# Ethernet_PHY.net
KiCad netlist of a schematic drawn in Altium Designer
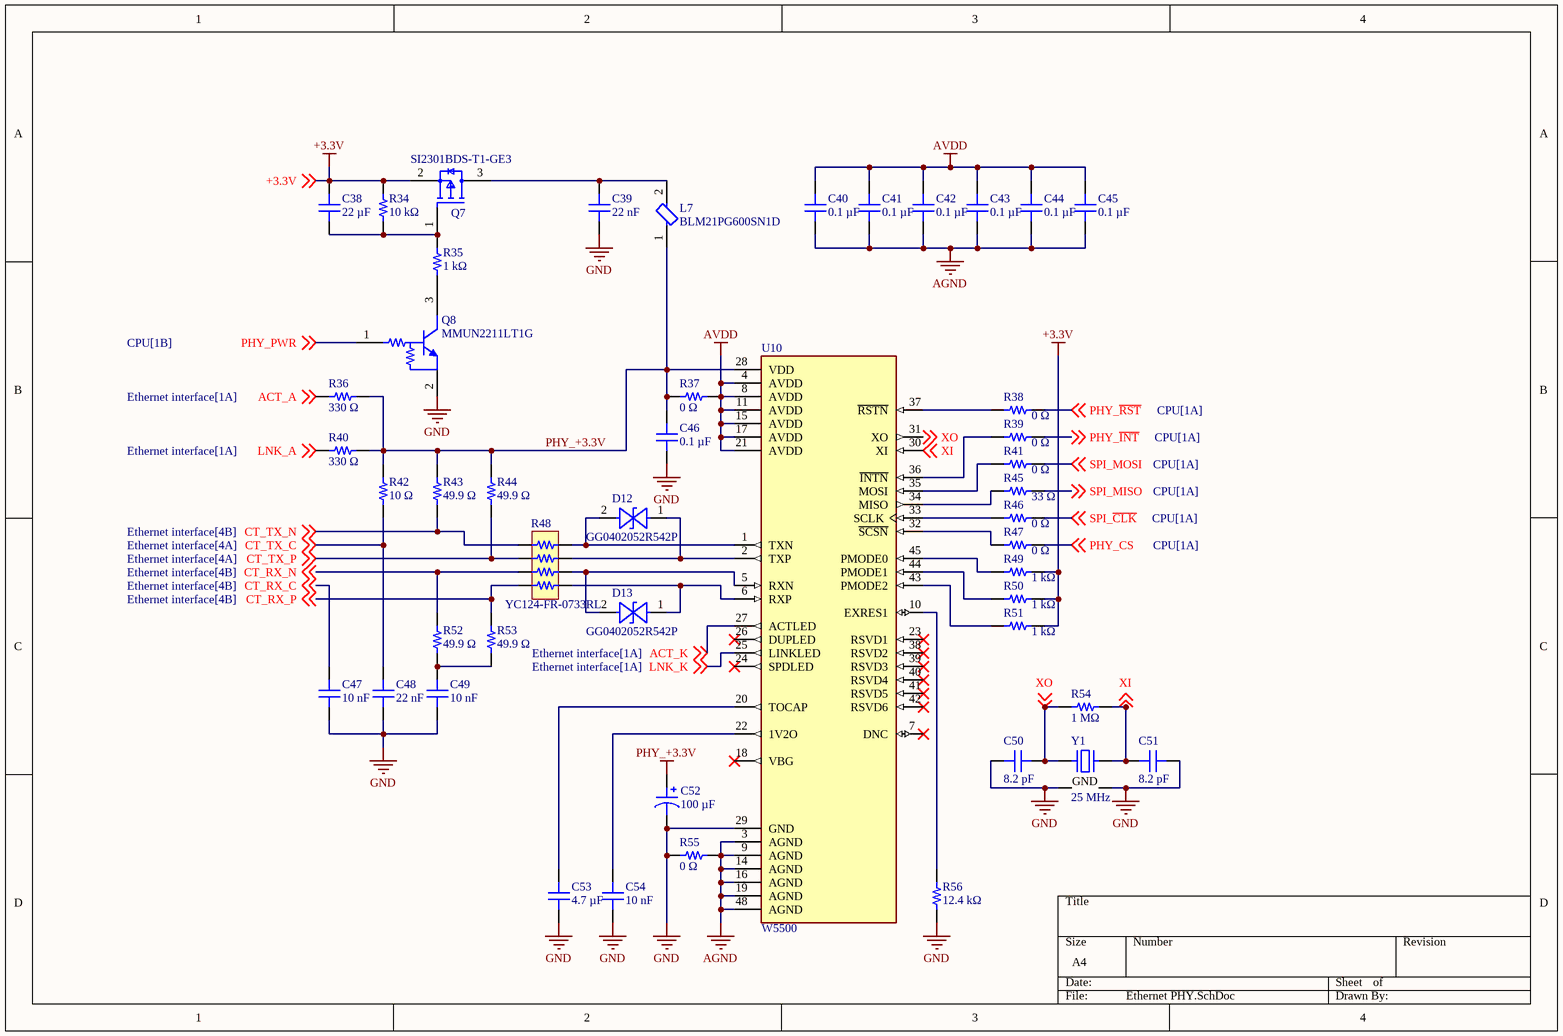
[diagram p0: Ethernet PHY.SchDoc]

(export (version "E")
  (design (tool "Eeschema 10.0.6"))
  (components
    (comp (ref "C38")
      (value "22 µF")
      (footprint "MURATA GRM188 0603_1608")
      (description "CAP CER 22UF 6.3V X5R 0603")
      (fields
        (field (name "PART NUMBER") "GRM186R60J226ME15D")
        (field (name "CAPACITANCE") "22 µF")
        (field (name "MANUFACTURER") "Murata Electronics")
      )
      (libsource (lib "Celestial Altium Library - altium_library") (part "Capacitor"))
    )
    (comp (ref "C39")
      (value "0.022 µF")
      (footprint "CAP 0603_1608")
      (description "CAP CER 0.022UF 50V X7R 0603")
      (fields
        (field (name "PART NUMBER") "C1608X7R1H223K080AE")
        (field (name "CAPACITANCE") "22 nF")
        (field (name "MANUFACTURER") "TDK Corporation")
      )
      (libsource (lib "Celestial Altium Library - altium_library") (part "Capacitor"))
    )
    (comp (ref "C40")
      (value "0.1 µF")
      (footprint "CAP 0603_1608")
      (description "CAP CER 0.1UF 50V X7R 0603")
      (fields
        (field (name "PART NUMBER") "C1608X7R1H104K080AE")
        (field (name "CAPACITANCE") "0.1 µF")
        (field (name "MANUFACTURER") "TDK Corporation")
      )
      (libsource (lib "Celestial Altium Library - altium_library") (part "Capacitor"))
    )
    (comp (ref "C41")
      (value "0.1 µF")
      (footprint "CAP 0603_1608")
      (description "CAP CER 0.1UF 50V X7R 0603")
      (fields
        (field (name "PART NUMBER") "C1608X7R1H104K080AE")
        (field (name "CAPACITANCE") "0.1 µF")
        (field (name "MANUFACTURER") "TDK Corporation")
      )
      (libsource (lib "Celestial Altium Library - altium_library") (part "Capacitor"))
    )
    (comp (ref "C42")
      (value "0.1 µF")
      (footprint "CAP 0603_1608")
      (description "CAP CER 0.1UF 50V X7R 0603")
      (fields
        (field (name "PART NUMBER") "C1608X7R1H104K080AE")
        (field (name "CAPACITANCE") "0.1 µF")
        (field (name "MANUFACTURER") "TDK Corporation")
      )
      (libsource (lib "Celestial Altium Library - altium_library") (part "Capacitor"))
    )
    (comp (ref "C43")
      (value "0.1 µF")
      (footprint "CAP 0603_1608")
      (description "CAP CER 0.1UF 50V X7R 0603")
      (fields
        (field (name "PART NUMBER") "C1608X7R1H104K080AE")
        (field (name "CAPACITANCE") "0.1 µF")
        (field (name "MANUFACTURER") "TDK Corporation")
      )
      (libsource (lib "Celestial Altium Library - altium_library") (part "Capacitor"))
    )
    (comp (ref "C44")
      (value "0.1 µF")
      (footprint "CAP 0603_1608")
      (description "CAP CER 0.1UF 50V X7R 0603")
      (fields
        (field (name "PART NUMBER") "C1608X7R1H104K080AE")
        (field (name "CAPACITANCE") "0.1 µF")
        (field (name "MANUFACTURER") "TDK Corporation")
      )
      (libsource (lib "Celestial Altium Library - altium_library") (part "Capacitor"))
    )
    (comp (ref "C45")
      (value "0.1 µF")
      (footprint "CAP 0603_1608")
      (description "CAP CER 0.1UF 50V X7R 0603")
      (fields
        (field (name "PART NUMBER") "C1608X7R1H104K080AE")
        (field (name "CAPACITANCE") "0.1 µF")
        (field (name "MANUFACTURER") "TDK Corporation")
      )
      (libsource (lib "Celestial Altium Library - altium_library") (part "Capacitor"))
    )
    (comp (ref "C46")
      (value "0.1 µF")
      (footprint "CAP 0603_1608")
      (description "CAP CER 0.1UF 50V X7R 0603")
      (fields
        (field (name "PART NUMBER") "C1608X7R1H104K080AE")
        (field (name "CAPACITANCE") "0.1 µF")
        (field (name "MANUFACTURER") "TDK Corporation")
      )
      (libsource (lib "Celestial Altium Library - altium_library") (part "Capacitor"))
    )
    (comp (ref "C47")
      (value "10000 pF")
      (footprint "CAP 0603_1608")
      (description "CAP CER 10000PF 50V X7R 0603")
      (fields
        (field (name "PART NUMBER") "C1608X7R1H103K080AE")
        (field (name "CAPACITANCE") "10 nF")
        (field (name "MANUFACTURER") "TDK Corporation")
      )
      (libsource (lib "Celestial Altium Library - altium_library") (part "Capacitor"))
    )
    (comp (ref "C48")
      (value "0.022 µF")
      (footprint "CAP 0603_1608")
      (description "CAP CER 0.022UF 50V X7R 0603")
      (fields
        (field (name "PART NUMBER") "C1608X7R1H223K080AE")
        (field (name "CAPACITANCE") "22 nF")
        (field (name "MANUFACTURER") "TDK Corporation")
      )
      (libsource (lib "Celestial Altium Library - altium_library") (part "Capacitor"))
    )
    (comp (ref "C49")
      (value "10000 pF")
      (footprint "CAP 0603_1608")
      (description "CAP CER 10000PF 50V X7R 0603")
      (fields
        (field (name "PART NUMBER") "C1608X7R1H103K080AE")
        (field (name "CAPACITANCE") "10 nF")
        (field (name "MANUFACTURER") "TDK Corporation")
      )
      (libsource (lib "Celestial Altium Library - altium_library") (part "Capacitor"))
    )
    (comp (ref "C50")
      (value "8.2 pF")
      (footprint "CAP 0603_1608")
      (description "CAP CER 8.2PF 50V C0G/NP0 0603")
      (fields
        (field (name "PART NUMBER") "C0603C829B5GACAUTO")
        (field (name "CAPACITANCE") "8.2 pF")
        (field (name "MANUFACTURER") "KEMET")
      )
      (libsource (lib "Celestial Altium Library - altium_library") (part "Capacitor"))
    )
    (comp (ref "C51")
      (value "8.2 pF")
      (footprint "CAP 0603_1608")
      (description "CAP CER 8.2PF 50V C0G/NP0 0603")
      (fields
        (field (name "PART NUMBER") "C0603C829B5GACAUTO")
        (field (name "CAPACITANCE") "8.2 pF")
        (field (name "MANUFACTURER") "KEMET")
      )
      (libsource (lib "Celestial Altium Library - altium_library") (part "Capacitor"))
    )
    (comp (ref "C52")
      (value "100 µF")
      (footprint "CAP POL 1411_3528")
      (description "CAP TANT 100UF 20% 6.3V 1411")
      (fields (field (name "PART NUMBER") "T494B107M006AT") (field (name "MANUFACTURER") "KEMET"))
      (libsource (lib "Celestial Altium Library - altium_library") (part "Polarised Capacitor"))
    )
    (comp (ref "C53")
      (value "4.7 µF")
      (footprint "CAP 0603_1608")
      (description "CAP CER 4.7UF 10V X5R 0603")
      (fields
        (field (name "PART NUMBER") "CL10A475KP8NNNC")
        (field (name "CAPACITANCE") "4.7 µF")
        (field (name "MANUFACTURER") "Samsung Electro-Mechanics")
      )
      (libsource (lib "Celestial Altium Library - altium_library") (part "Capacitor"))
    )
    (comp (ref "C54")
      (value "10000 pF")
      (footprint "CAP 0603_1608")
      (description "CAP CER 10000PF 50V X7R 0603")
      (fields
        (field (name "PART NUMBER") "C1608X7R1H103K080AE")
        (field (name "CAPACITANCE") "10 nF")
        (field (name "MANUFACTURER") "TDK Corporation")
      )
      (libsource (lib "Celestial Altium Library - altium_library") (part "Capacitor"))
    )
    (comp (ref "D12")
      (value "GG0402052R542P")
      (footprint "TVS_GG0402_KAV")
      (description "Description")
      (fields (field (name "COPYRIGHT") "Copyright (C) 2025 Ultra Librarian. All rights reserved."))
      (libsource (lib "SchLib") (part "GG0402052R542P"))
    )
    (comp (ref "D13")
      (value "GG0402052R542P")
      (footprint "TVS_GG0402_KAV")
      (description "Description")
      (fields (field (name "COPYRIGHT") "Copyright (C) 2025 Ultra Librarian. All rights reserved."))
      (libsource (lib "SchLib") (part "GG0402052R542P"))
    )
    (comp (ref "L7")
      (value "BLM21PG600SN1D")
      (footprint "FP-BLM21-0_2-t0_85-e0_5-d-IPC_A")
      (description "Chip Ferrite Bead, 0805, 60Ω @ 100MHz, 0.02Ω, 25%, 3.5A")
      (fields (field (name "TOLERANCE") "25%"))
      (libsource (lib "Altium Content Vault") (part "5f30dd21d616792df468990f7003faa"))
    )
    (comp (ref "Q7")
      (value "SI2301BDS-T1-GE3")
      (footprint "FP-S-03946-MFG")
      (description "SI2301BDS-T1-GE3 Trans Mosfet P-ch Si 20V 2.2A 3-PIN SOT-23 T/r / Mosfet P-ch 20V 2.2A SOT23-3")
      (libsource (lib "Altium Content Vault") (part "274ba75a4227b453460520a6808ef61"))
    )
    (comp (ref "Q8")
      (value "MMUN2211LT1G")
      (footprint "ONSC-SOT-23-3-318-08_V")
      (fields (field (name "PARTNUMBER") "SMMUN2211LT1G") (field (name "MANUFACTURER") "On Semiconductor"))
      (libsource (lib "Altium Content Vault") (part "ONSC-BRT-NPN-B1E2C3-3"))
    )
    (comp (ref "R34")
      (value "10 kΩ")
      (footprint "RES 0603_1608")
      (description "RES SMD 10K OHM 1% 1/10W 0603")
      (fields (field (name "PART NUMBER") "CRCW060310K0FKEA") (field (name "MANUFACTURER") "Vishay Dale"))
      (libsource (lib "Celestial Altium Library - altium_library") (part "Resistor"))
    )
    (comp (ref "R35")
      (value "1 kΩ")
      (footprint "RES 0603_1608")
      (description "RES SMD 1K OHM 1% 1/10W 0603")
      (fields (field (name "PART NUMBER") "CRCW06031K00FKEA") (field (name "MANUFACTURER") "Vishay Dale"))
      (libsource (lib "Celestial Altium Library - altium_library") (part "Resistor"))
    )
    (comp (ref "R36")
      (value "330 Ω")
      (footprint "RES 0603_1608")
      (description "RES SMD 330 OHM 1% 1/10W 0603")
      (fields (field (name "PART NUMBER") "CRCW0603330RFKEA") (field (name "MANUFACTURER") "Vishay Dale"))
      (libsource (lib "Celestial Altium Library - altium_library") (part "Resistor"))
    )
    (comp (ref "R37")
      (value "0 Ω")
      (footprint "RES 0603_1608")
      (description "RES SMD 0 OHM JUMPER 1/10W 0603")
      (fields
        (field (name "PART NUMBER") "ERJ-3GEY0R00V")
        (field (name "MANUFACTURER") "Panasonic Electronic Components")
      )
      (libsource (lib "Celestial Altium Library - altium_library") (part "Resistor"))
    )
    (comp (ref "R38")
      (value "0 Ω")
      (footprint "RES 0603_1608")
      (description "RES SMD 0 OHM JUMPER 1/10W 0603")
      (fields
        (field (name "PART NUMBER") "ERJ-3GEY0R00V")
        (field (name "MANUFACTURER") "Panasonic Electronic Components")
      )
      (libsource (lib "Celestial Altium Library - altium_library") (part "Resistor"))
    )
    (comp (ref "R39")
      (value "0 Ω")
      (footprint "RES 0603_1608")
      (description "RES SMD 0 OHM JUMPER 1/10W 0603")
      (fields
        (field (name "PART NUMBER") "ERJ-3GEY0R00V")
        (field (name "MANUFACTURER") "Panasonic Electronic Components")
      )
      (libsource (lib "Celestial Altium Library - altium_library") (part "Resistor"))
    )
    (comp (ref "R40")
      (value "330 Ω")
      (footprint "RES 0603_1608")
      (description "RES SMD 330 OHM 1% 1/10W 0603")
      (fields (field (name "PART NUMBER") "CRCW0603330RFKEA") (field (name "MANUFACTURER") "Vishay Dale"))
      (libsource (lib "Celestial Altium Library - altium_library") (part "Resistor"))
    )
    (comp (ref "R41")
      (value "0 Ω")
      (footprint "RES 0603_1608")
      (description "RES SMD 0 OHM JUMPER 1/10W 0603")
      (fields
        (field (name "PART NUMBER") "ERJ-3GEY0R00V")
        (field (name "MANUFACTURER") "Panasonic Electronic Components")
      )
      (libsource (lib "Celestial Altium Library - altium_library") (part "Resistor"))
    )
    (comp (ref "R42")
      (value "10 Ω")
      (footprint "RES 0603_1608")
      (description "RES SMD 10 OHM 1% 1/10W 0603")
      (fields (field (name "PART NUMBER") "CRCW060310R0FKEA") (field (name "MANUFACTURER") "Vishay Dale"))
      (libsource (lib "Celestial Altium Library - altium_library") (part "Resistor"))
    )
    (comp (ref "R43")
      (value "49.9 Ω")
      (footprint "RES 0603_1608")
      (description "RES SMD 49.9 OHM 1% 1/10W 0603")
      (fields (field (name "PART NUMBER") "CRCW060349R9FKEA") (field (name "MANUFACTURER") "Vishay Dale"))
      (libsource (lib "Celestial Altium Library - altium_library") (part "Resistor"))
    )
    (comp (ref "R44")
      (value "49.9 Ω")
      (footprint "RES 0603_1608")
      (description "RES SMD 49.9 OHM 1% 1/10W 0603")
      (fields (field (name "PART NUMBER") "CRCW060349R9FKEA") (field (name "MANUFACTURER") "Vishay Dale"))
      (libsource (lib "Celestial Altium Library - altium_library") (part "Resistor"))
    )
    (comp (ref "R45")
      (value "33 Ω")
      (footprint "RES 0603_1608")
      (description "RES 33 OHM 1% 1/10W 0603")
      (fields
        (field (name "PART NUMBER") "RMCF0603FT33R0")
        (field (name "MANUFACTURER") "Stackpole Electronics Inc")
      )
      (libsource (lib "Celestial Altium Library - altium_library") (part "Resistor"))
    )
    (comp (ref "R46")
      (value "0 Ω")
      (footprint "RES 0603_1608")
      (description "RES SMD 0 OHM JUMPER 1/10W 0603")
      (fields
        (field (name "PART NUMBER") "ERJ-3GEY0R00V")
        (field (name "MANUFACTURER") "Panasonic Electronic Components")
      )
      (libsource (lib "Celestial Altium Library - altium_library") (part "Resistor"))
    )
    (comp (ref "R47")
      (value "0 Ω")
      (footprint "RES 0603_1608")
      (description "RES SMD 0 OHM JUMPER 1/10W 0603")
      (fields
        (field (name "PART NUMBER") "ERJ-3GEY0R00V")
        (field (name "MANUFACTURER") "Panasonic Electronic Components")
      )
      (libsource (lib "Celestial Altium Library - altium_library") (part "Resistor"))
    )
    (comp (ref "R48")
      (value "YC124-FR-0733RL")
      (footprint "RESNET 0804-8 CONVEX")
      (description "RES ARRAY 4 RES 33 OHM 0804")
      (fields (field (name "MANUFACTURER") "Yageo") (field (name "TOLERANCE") "±1%"))
      (libsource (lib "Celestial Altium Library - altium_library") (part "Resistor Array (4 circuit)"))
    )
    (comp (ref "R49")
      (value "1 kΩ")
      (footprint "RES 0603_1608")
      (description "RES SMD 1K OHM 1% 1/10W 0603")
      (fields (field (name "PART NUMBER") "CRCW06031K00FKEA") (field (name "MANUFACTURER") "Vishay Dale"))
      (libsource (lib "Celestial Altium Library - altium_library") (part "Resistor"))
    )
    (comp (ref "R50")
      (value "1 kΩ")
      (footprint "RES 0603_1608")
      (description "RES SMD 1K OHM 1% 1/10W 0603")
      (fields (field (name "PART NUMBER") "CRCW06031K00FKEA") (field (name "MANUFACTURER") "Vishay Dale"))
      (libsource (lib "Celestial Altium Library - altium_library") (part "Resistor"))
    )
    (comp (ref "R51")
      (value "1 kΩ")
      (footprint "RES 0603_1608")
      (description "RES SMD 1K OHM 1% 1/10W 0603")
      (fields (field (name "PART NUMBER") "CRCW06031K00FKEA") (field (name "MANUFACTURER") "Vishay Dale"))
      (libsource (lib "Celestial Altium Library - altium_library") (part "Resistor"))
    )
    (comp (ref "R52")
      (value "49.9 Ω")
      (footprint "RES 0603_1608")
      (description "RES SMD 49.9 OHM 1% 1/10W 0603")
      (fields (field (name "PART NUMBER") "CRCW060349R9FKEA") (field (name "MANUFACTURER") "Vishay Dale"))
      (libsource (lib "Celestial Altium Library - altium_library") (part "Resistor"))
    )
    (comp (ref "R53")
      (value "49.9 Ω")
      (footprint "RES 0603_1608")
      (description "RES SMD 49.9 OHM 1% 1/10W 0603")
      (fields (field (name "PART NUMBER") "CRCW060349R9FKEA") (field (name "MANUFACTURER") "Vishay Dale"))
      (libsource (lib "Celestial Altium Library - altium_library") (part "Resistor"))
    )
    (comp (ref "R54")
      (value "1 MΩ")
      (footprint "RES 0603_1608")
      (description "RES SMD 1M OHM 1% 1/10W 0603")
      (fields (field (name "PART NUMBER") "CRCW06031M00FKEA") (field (name "MANUFACTURER") "Vishay Dale"))
      (libsource (lib "Celestial Altium Library - altium_library") (part "Resistor"))
    )
    (comp (ref "R55")
      (value "0 Ω")
      (footprint "RES 0603_1608")
      (description "RES SMD 0 OHM JUMPER 1/10W 0603")
      (fields
        (field (name "PART NUMBER") "ERJ-3GEY0R00V")
        (field (name "MANUFACTURER") "Panasonic Electronic Components")
      )
      (libsource (lib "Celestial Altium Library - altium_library") (part "Resistor"))
    )
    (comp (ref "R56")
      (value "12.4 kΩ")
      (footprint "RES 0603_1608")
      (description "RES SMD 12.4K OHM 1% 1/10W 0603")
      (fields (field (name "PART NUMBER") "CRCW060312K4FKEA") (field (name "MANUFACTURER") "Vishay Dale"))
      (libsource (lib "Celestial Altium Library - altium_library") (part "Resistor"))
    )
    (comp (ref "U10")
      (value "W5500")
      (footprint "mpair:LQFP-48N")
      (description "Hardwired TCP/IP embedded Ethernet controller")
      (libsource (lib "SchLib") (part "W5500"))
    )
    (comp (ref "Y1")
      (value "25 MHz")
      (footprint "NDK NX2520SA")
      (description "CRYSTAL 25.0000MHZ 8PF SMD")
      (fields (field (name "PART NUMBER") "STDCSW5-25M") (field (name "MANUFACTURER") "NDK America, Inc."))
      (libsource (lib "Celestial Altium Library - altium_library") (part "NDK Crystal NX2520SA"))
    )
  )
  (nets
    (net (code "1") (name "+3.3V") (class "Default")
      (node (ref "C38") (pin "2") (pinfunction "2_2") (pintype "passive"))
      (node (ref "Q7") (pin "2") (pinfunction "S_2") (pintype "passive"))
      (node (ref "R34") (pin "2") (pinfunction "2_2") (pintype "passive"))
      (node (ref "R49") (pin "2") (pinfunction "2_2") (pintype "passive"))
      (node (ref "R50") (pin "2") (pinfunction "2_2") (pintype "passive"))
      (node (ref "R51") (pin "2") (pinfunction "2_2") (pintype "passive"))
    )
    (net (code "2") (name "ACT_A") (class "Default")
      (node (ref "R36") (pin "1") (pinfunction "1_1") (pintype "passive"))
    )
    (net (code "3") (name "ACT_K") (class "Default")
      (node (ref "U10") (pin "27") (pinfunction "ACTLED_27") (pintype "output"))
    )
    (net (code "4") (name "AGND") (class "Default")
      (node (ref "C40") (pin "1") (pinfunction "1_1") (pintype "passive"))
      (node (ref "C41") (pin "1") (pinfunction "1_1") (pintype "passive"))
      (node (ref "C42") (pin "1") (pinfunction "1_1") (pintype "passive"))
      (node (ref "C43") (pin "1") (pinfunction "1_1") (pintype "passive"))
      (node (ref "C44") (pin "1") (pinfunction "1_1") (pintype "passive"))
      (node (ref "C45") (pin "1") (pinfunction "1_1") (pintype "passive"))
      (node (ref "R55") (pin "2") (pinfunction "2_2") (pintype "passive"))
      (node (ref "U10") (pin "14") (pinfunction "AGND_14") (pintype "power_in"))
      (node (ref "U10") (pin "16") (pinfunction "AGND_16") (pintype "power_in"))
      (node (ref "U10") (pin "19") (pinfunction "AGND_19") (pintype "power_in"))
      (node (ref "U10") (pin "3") (pinfunction "AGND_3") (pintype "power_in"))
      (node (ref "U10") (pin "48") (pinfunction "AGND_48") (pintype "power_in"))
      (node (ref "U10") (pin "9") (pinfunction "AGND_9") (pintype "power_in"))
    )
    (net (code "5") (name "AVDD") (class "Default")
      (node (ref "C40") (pin "2") (pinfunction "2_2") (pintype "passive"))
      (node (ref "C41") (pin "2") (pinfunction "2_2") (pintype "passive"))
      (node (ref "C42") (pin "2") (pinfunction "2_2") (pintype "passive"))
      (node (ref "C43") (pin "2") (pinfunction "2_2") (pintype "passive"))
      (node (ref "C44") (pin "2") (pinfunction "2_2") (pintype "passive"))
      (node (ref "C45") (pin "2") (pinfunction "2_2") (pintype "passive"))
      (node (ref "R37") (pin "2") (pinfunction "2_2") (pintype "passive"))
      (node (ref "U10") (pin "11") (pinfunction "AVDD_11") (pintype "power_in"))
      (node (ref "U10") (pin "15") (pinfunction "AVDD_15") (pintype "power_in"))
      (node (ref "U10") (pin "17") (pinfunction "AVDD_17") (pintype "power_in"))
      (node (ref "U10") (pin "21") (pinfunction "AVDD_21") (pintype "power_in"))
      (node (ref "U10") (pin "4") (pinfunction "AVDD_4") (pintype "power_in"))
      (node (ref "U10") (pin "8") (pinfunction "AVDD_8") (pintype "power_in"))
    )
    (net (code "6") (name "CT_RX_C") (class "Default")
      (node (ref "C47") (pin "1") (pinfunction "1_1") (pintype "passive"))
    )
    (net (code "7") (name "CT_RX_N") (class "Default")
      (node (ref "R48") (pin "3") (pinfunction "3_3") (pintype "passive"))
      (node (ref "R52") (pin "2") (pinfunction "2_2") (pintype "passive"))
    )
    (net (code "8") (name "CT_RX_P") (class "Default")
      (node (ref "R48") (pin "4") (pinfunction "4_4") (pintype "passive"))
      (node (ref "R53") (pin "2") (pinfunction "2_2") (pintype "passive"))
    )
    (net (code "9") (name "CT_TX_C") (class "Default")
      (node (ref "C48") (pin "2") (pinfunction "2_2") (pintype "passive"))
      (node (ref "R42") (pin "1") (pinfunction "1_1") (pintype "passive"))
    )
    (net (code "10") (name "CT_TX_N") (class "Default")
      (node (ref "R43") (pin "1") (pinfunction "1_1") (pintype "passive"))
      (node (ref "R48") (pin "1") (pinfunction "1_1") (pintype "passive"))
    )
    (net (code "11") (name "CT_TX_P") (class "Default")
      (node (ref "R44") (pin "1") (pinfunction "1_1") (pintype "passive"))
      (node (ref "R48") (pin "2") (pinfunction "2_2") (pintype "passive"))
    )
    (net (code "12") (name "GND") (class "Default")
      (node (ref "C39") (pin "1") (pinfunction "1_1") (pintype "passive"))
      (node (ref "C46") (pin "1") (pinfunction "1_1") (pintype "passive"))
      (node (ref "C47") (pin "2") (pinfunction "2_2") (pintype "passive"))
      (node (ref "C48") (pin "1") (pinfunction "1_1") (pintype "passive"))
      (node (ref "C49") (pin "2") (pinfunction "2_2") (pintype "passive"))
      (node (ref "C50") (pin "2") (pinfunction "2_2") (pintype "passive"))
      (node (ref "C51") (pin "1") (pinfunction "1_1") (pintype "passive"))
      (node (ref "C52") (pin "2") (pinfunction "2_2") (pintype "passive"))
      (node (ref "C53") (pin "1") (pinfunction "1_1") (pintype "passive"))
      (node (ref "C54") (pin "2") (pinfunction "2_2") (pintype "passive"))
      (node (ref "Q8") (pin "2") (pinfunction "E_2") (pintype "passive"))
      (node (ref "R55") (pin "1") (pinfunction "1_1") (pintype "passive"))
      (node (ref "R56") (pin "1") (pinfunction "1_1") (pintype "passive"))
      (node (ref "U10") (pin "29") (pinfunction "GND_29") (pintype "passive"))
      (node (ref "Y1") (pin "2") (pinfunction "GND_2") (pintype "passive"))
      (node (ref "Y1") (pin "4") (pinfunction "GND_4") (pintype "passive"))
    )
    (net (code "13") (name "LNK_A") (class "Default")
      (node (ref "R40") (pin "1") (pinfunction "1_1") (pintype "passive"))
    )
    (net (code "14") (name "LNK_K") (class "Default")
      (node (ref "U10") (pin "25") (pinfunction "LINKLED_25") (pintype "output"))
    )
    (net (code "15") (name "Net-(C49-Pad1)") (class "Default")
      (node (ref "C49") (pin "1") (pinfunction "1_1") (pintype "passive"))
      (node (ref "R52") (pin "1") (pinfunction "1_1") (pintype "passive"))
      (node (ref "R53") (pin "1") (pinfunction "1_1") (pintype "passive"))
    )
    (net (code "16") (name "Net-(D12-ANODECATHODE)") (class "Default")
      (node (ref "D12") (pin "1") (pinfunction "ANODECATHODE_1") (pintype "passive"))
      (node (ref "R48") (pin "7") (pinfunction "7_7") (pintype "passive"))
      (node (ref "U10") (pin "2") (pinfunction "TXP_2") (pintype "output"))
    )
    (net (code "17") (name "Net-(D12-CATHODEANODE)") (class "Default")
      (node (ref "D12") (pin "2") (pinfunction "CATHODEANODE_2") (pintype "passive"))
      (node (ref "R48") (pin "8") (pinfunction "8_8") (pintype "passive"))
      (node (ref "U10") (pin "1") (pinfunction "TXN_1") (pintype "output"))
    )
    (net (code "18") (name "Net-(D13-ANODECATHODE)") (class "Default")
      (node (ref "D13") (pin "1") (pinfunction "ANODECATHODE_1") (pintype "passive"))
      (node (ref "R48") (pin "5") (pinfunction "5_5") (pintype "passive"))
      (node (ref "U10") (pin "6") (pinfunction "RXP_6") (pintype "input"))
    )
    (net (code "19") (name "Net-(D13-CATHODEANODE)") (class "Default")
      (node (ref "D13") (pin "2") (pinfunction "CATHODEANODE_2") (pintype "passive"))
      (node (ref "R48") (pin "6") (pinfunction "6_6") (pintype "passive"))
      (node (ref "U10") (pin "5") (pinfunction "RXN_5") (pintype "input"))
    )
    (net (code "20") (name "Net-(Q7-D)") (class "Default")
      (node (ref "C39") (pin "2") (pinfunction "2_2") (pintype "passive"))
      (node (ref "L7") (pin "2") (pinfunction "2_2") (pintype "passive"))
      (node (ref "Q7") (pin "3") (pinfunction "D_3") (pintype "passive"))
    )
    (net (code "21") (name "Net-(Q7-G)") (class "Default")
      (node (ref "C38") (pin "1") (pinfunction "1_1") (pintype "passive"))
      (node (ref "Q7") (pin "1") (pinfunction "G_1") (pintype "passive"))
      (node (ref "R34") (pin "1") (pinfunction "1_1") (pintype "passive"))
      (node (ref "R35") (pin "2") (pinfunction "2_2") (pintype "passive"))
    )
    (net (code "22") (name "Net-(Q8-C)") (class "Default")
      (node (ref "Q8") (pin "3") (pinfunction "C_3") (pintype "passive"))
      (node (ref "R35") (pin "1") (pinfunction "1_1") (pintype "passive"))
    )
    (net (code "23") (name "Net-(U10-1V2O)") (class "Default")
      (node (ref "C54") (pin "1") (pinfunction "1_1") (pintype "passive"))
      (node (ref "U10") (pin "22") (pinfunction "1V2O_22") (pintype "output"))
    )
    (net (code "24") (name "Net-(U10-EXRES1)") (class "Default")
      (node (ref "R56") (pin "2") (pinfunction "2_2") (pintype "passive"))
      (node (ref "U10") (pin "10") (pinfunction "EXRES1_10") (pintype "bidirectional"))
    )
    (net (code "25") (name "Net-(U10-MISO)") (class "Default")
      (node (ref "R45") (pin "1") (pinfunction "1_1") (pintype "passive"))
      (node (ref "U10") (pin "34") (pinfunction "MISO_34") (pintype "output"))
    )
    (net (code "26") (name "Net-(U10-MOSI)") (class "Default")
      (node (ref "R41") (pin "1") (pinfunction "1_1") (pintype "passive"))
      (node (ref "U10") (pin "35") (pinfunction "MOSI_35") (pintype "input"))
    )
    (net (code "27") (name "Net-(U10-PMODE0)") (class "Default")
      (node (ref "R49") (pin "1") (pinfunction "1_1") (pintype "passive"))
      (node (ref "U10") (pin "45") (pinfunction "PMODE0_45") (pintype "input"))
    )
    (net (code "28") (name "Net-(U10-PMODE1)") (class "Default")
      (node (ref "R50") (pin "1") (pinfunction "1_1") (pintype "passive"))
      (node (ref "U10") (pin "44") (pinfunction "PMODE1_44") (pintype "input"))
    )
    (net (code "29") (name "Net-(U10-PMODE2)") (class "Default")
      (node (ref "R51") (pin "1") (pinfunction "1_1") (pintype "passive"))
      (node (ref "U10") (pin "43") (pinfunction "PMODE2_43") (pintype "input"))
    )
    (net (code "30") (name "Net-(U10-SCLK)") (class "Default")
      (node (ref "R46") (pin "1") (pinfunction "1_1") (pintype "passive"))
      (node (ref "U10") (pin "33") (pinfunction "SCLK_33") (pintype "input"))
    )
    (net (code "31") (name "Net-(U10-TOCAP)") (class "Default")
      (node (ref "C53") (pin "2") (pinfunction "2_2") (pintype "passive"))
      (node (ref "U10") (pin "20") (pinfunction "TOCAP_20") (pintype "output"))
    )
    (net (code "32") (name "Net-(U10-~{INTN})") (class "Default")
      (node (ref "R39") (pin "1") (pinfunction "1_1") (pintype "passive"))
      (node (ref "U10") (pin "36") (pinfunction "~{INTN}_36") (pintype "input"))
    )
    (net (code "33") (name "Net-(U10-~{RSTN})") (class "Default")
      (node (ref "R38") (pin "1") (pinfunction "1_1") (pintype "passive"))
      (node (ref "U10") (pin "37") (pinfunction "~{RSTN}_37") (pintype "input"))
    )
    (net (code "34") (name "Net-(U10-~{SCSN})") (class "Default")
      (node (ref "R47") (pin "1") (pinfunction "1_1") (pintype "passive"))
      (node (ref "U10") (pin "32") (pinfunction "~{SCSN}_32") (pintype "input"))
    )
    (net (code "35") (name "PHY_+3.3V") (class "Default")
      (node (ref "C46") (pin "2") (pinfunction "2_2") (pintype "passive"))
      (node (ref "C52") (pin "1") (pinfunction "1_1") (pintype "passive"))
      (node (ref "L7") (pin "1") (pinfunction "1_1") (pintype "passive"))
      (node (ref "R36") (pin "2") (pinfunction "2_2") (pintype "passive"))
      (node (ref "R37") (pin "1") (pinfunction "1_1") (pintype "passive"))
      (node (ref "R40") (pin "2") (pinfunction "2_2") (pintype "passive"))
      (node (ref "R42") (pin "2") (pinfunction "2_2") (pintype "passive"))
      (node (ref "R43") (pin "2") (pinfunction "2_2") (pintype "passive"))
      (node (ref "R44") (pin "2") (pinfunction "2_2") (pintype "passive"))
      (node (ref "U10") (pin "28") (pinfunction "VDD_28") (pintype "power_in"))
    )
    (net (code "36") (name "PHY_CS") (class "Default")
      (node (ref "R47") (pin "2") (pinfunction "2_2") (pintype "passive"))
    )
    (net (code "37") (name "PHY_PWR") (class "Default")
      (node (ref "Q8") (pin "1") (pinfunction "B_1") (pintype "passive"))
    )
    (net (code "38") (name "PHY_~{INT}") (class "Default")
      (node (ref "R39") (pin "2") (pinfunction "2_2") (pintype "passive"))
    )
    (net (code "39") (name "PHY_~{RST}") (class "Default")
      (node (ref "R38") (pin "2") (pinfunction "2_2") (pintype "passive"))
    )
    (net (code "40") (name "SPI_MISO") (class "Default")
      (node (ref "R45") (pin "2") (pinfunction "2_2") (pintype "passive"))
    )
    (net (code "41") (name "SPI_MOSI") (class "Default")
      (node (ref "R41") (pin "2") (pinfunction "2_2") (pintype "passive"))
    )
    (net (code "42") (name "SPI_~{CLK}") (class "Default")
      (node (ref "R46") (pin "2") (pinfunction "2_2") (pintype "passive"))
    )
    (net (code "43") (name "XI") (class "Default")
      (node (ref "C51") (pin "2") (pinfunction "2_2") (pintype "passive"))
      (node (ref "R54") (pin "2") (pinfunction "2_2") (pintype "passive"))
      (node (ref "U10") (pin "30") (pinfunction "XI_30") (pintype "input"))
      (node (ref "Y1") (pin "3") (pinfunction "3_3") (pintype "passive"))
    )
    (net (code "44") (name "XO") (class "Default")
      (node (ref "C50") (pin "1") (pinfunction "1_1") (pintype "passive"))
      (node (ref "R54") (pin "1") (pinfunction "1_1") (pintype "passive"))
      (node (ref "U10") (pin "31") (pinfunction "XO_31") (pintype "output"))
      (node (ref "Y1") (pin "1") (pinfunction "1_1") (pintype "passive"))
    )
    (net (code "45") (name "unconnected-(U10-DNC-Pad7)") (class "Default")
      (node (ref "U10") (pin "7") (pinfunction "DNC_7") (pintype "bidirectional+no_connect"))
    )
    (net (code "46") (name "unconnected-(U10-DUPLED-Pad26)") (class "Default")
      (node (ref "U10") (pin "26") (pinfunction "DUPLED_26") (pintype "output+no_connect"))
    )
    (net (code "47") (name "unconnected-(U10-RSVD1-Pad23)") (class "Default")
      (node (ref "U10") (pin "23") (pinfunction "RSVD1_23") (pintype "input+no_connect"))
    )
    (net (code "48") (name "unconnected-(U10-RSVD2-Pad38)") (class "Default")
      (node (ref "U10") (pin "38") (pinfunction "RSVD2_38") (pintype "input+no_connect"))
    )
    (net (code "49") (name "unconnected-(U10-RSVD3-Pad39)") (class "Default")
      (node (ref "U10") (pin "39") (pinfunction "RSVD3_39") (pintype "input+no_connect"))
    )
    (net (code "50") (name "unconnected-(U10-RSVD4-Pad40)") (class "Default")
      (node (ref "U10") (pin "40") (pinfunction "RSVD4_40") (pintype "input+no_connect"))
    )
    (net (code "51") (name "unconnected-(U10-RSVD5-Pad41)") (class "Default")
      (node (ref "U10") (pin "41") (pinfunction "RSVD5_41") (pintype "input+no_connect"))
    )
    (net (code "52") (name "unconnected-(U10-RSVD6-Pad42)") (class "Default")
      (node (ref "U10") (pin "42") (pinfunction "RSVD6_42") (pintype "input+no_connect"))
    )
    (net (code "53") (name "unconnected-(U10-SPDLED-Pad24)") (class "Default")
      (node (ref "U10") (pin "24") (pinfunction "SPDLED_24") (pintype "output+no_connect"))
    )
    (net (code "54") (name "unconnected-(U10-VBG-Pad18)") (class "Default")
      (node (ref "U10") (pin "18") (pinfunction "VBG_18") (pintype "output+no_connect"))
    )
  )
)
